# PixelRing.net
KiCad netlist of a schematic drawn in EAGLE
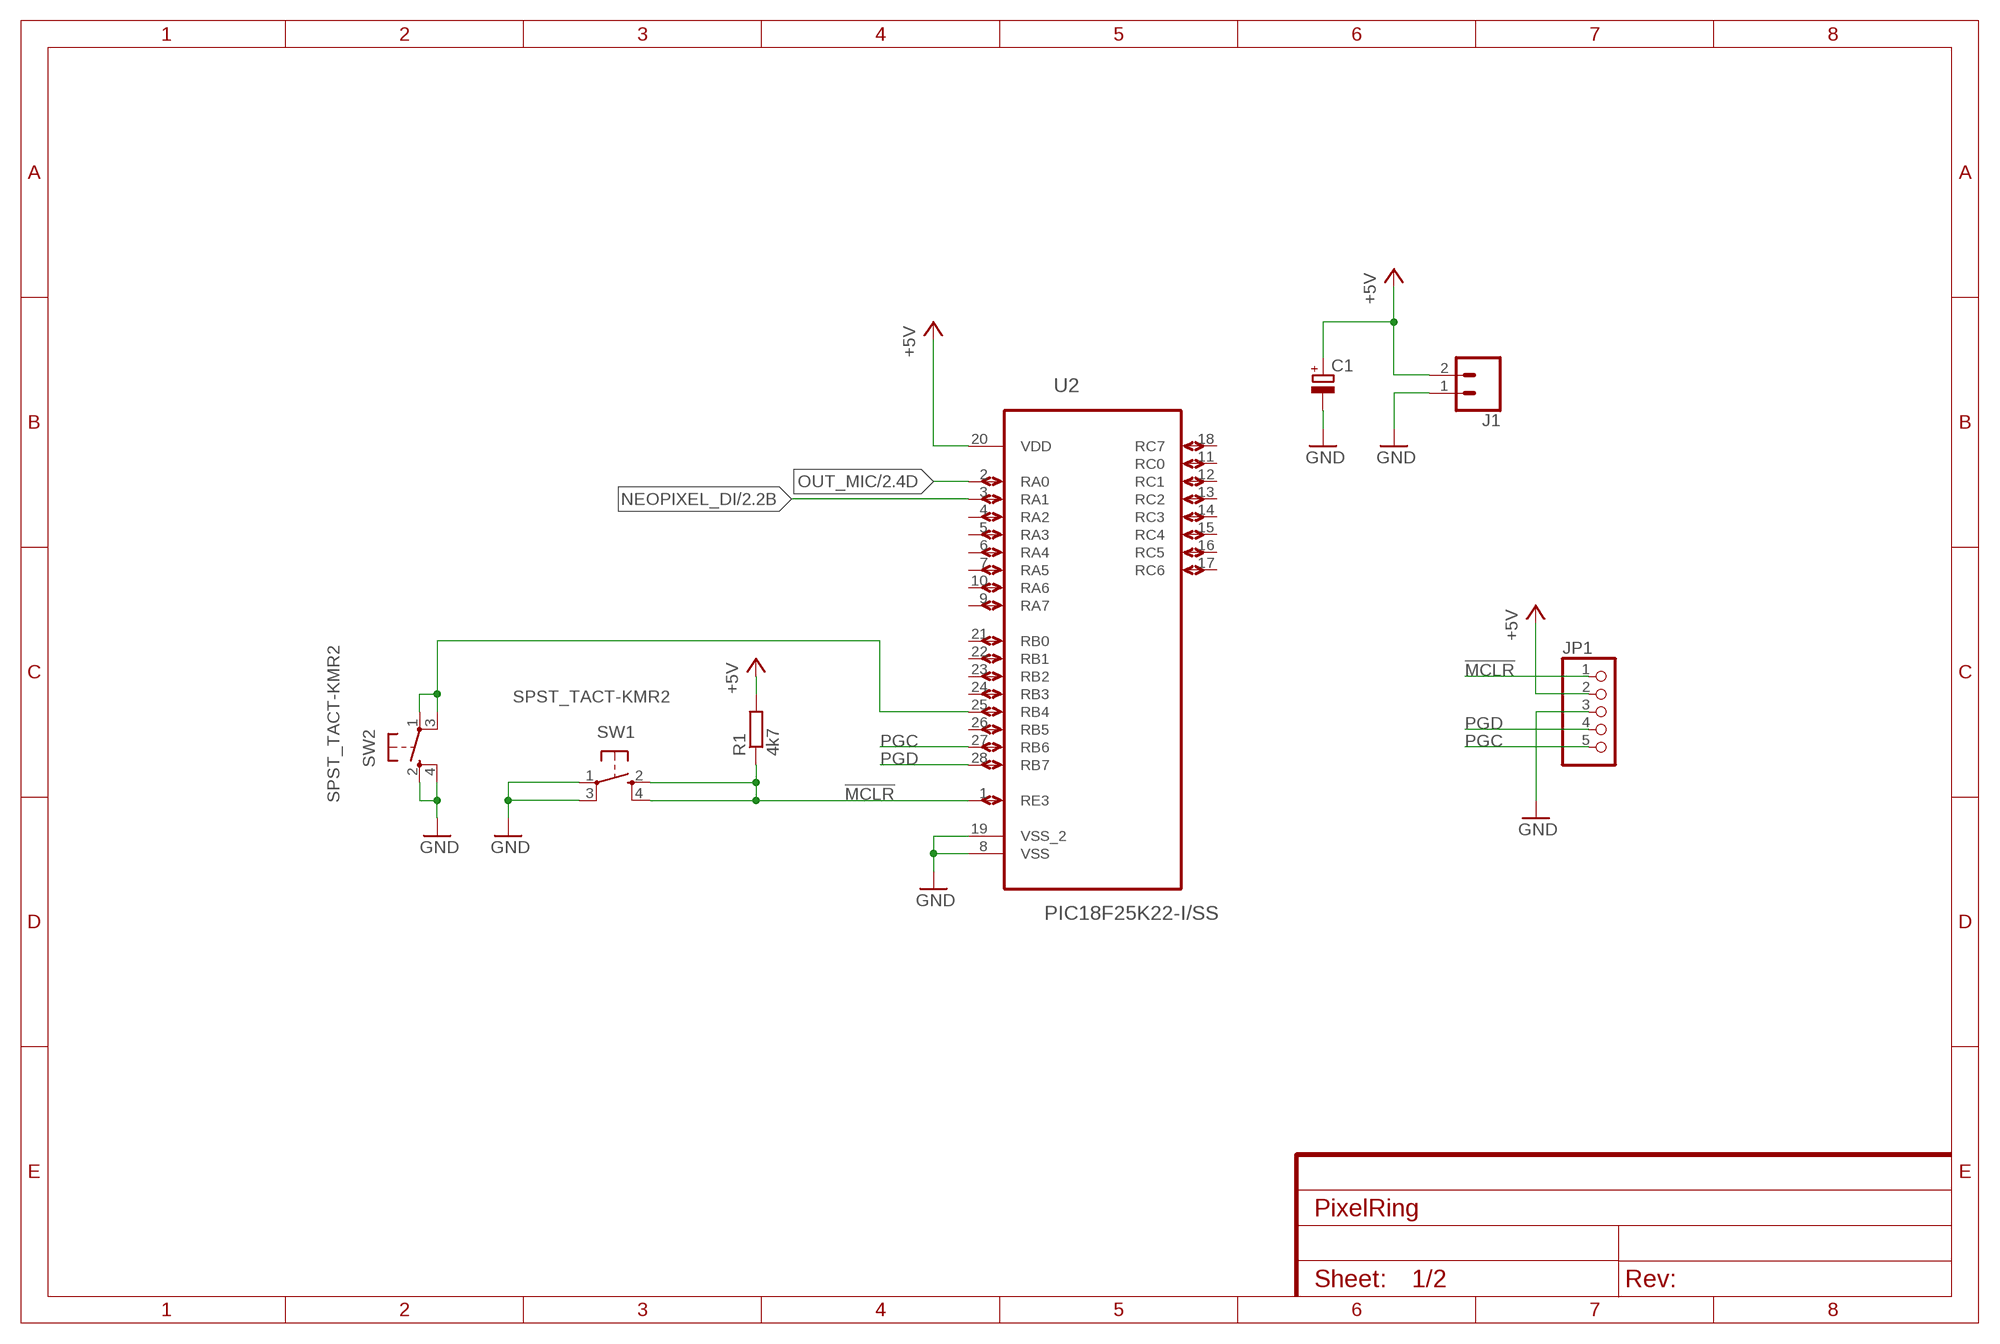
[diagram p0: schematic, sheet 1]
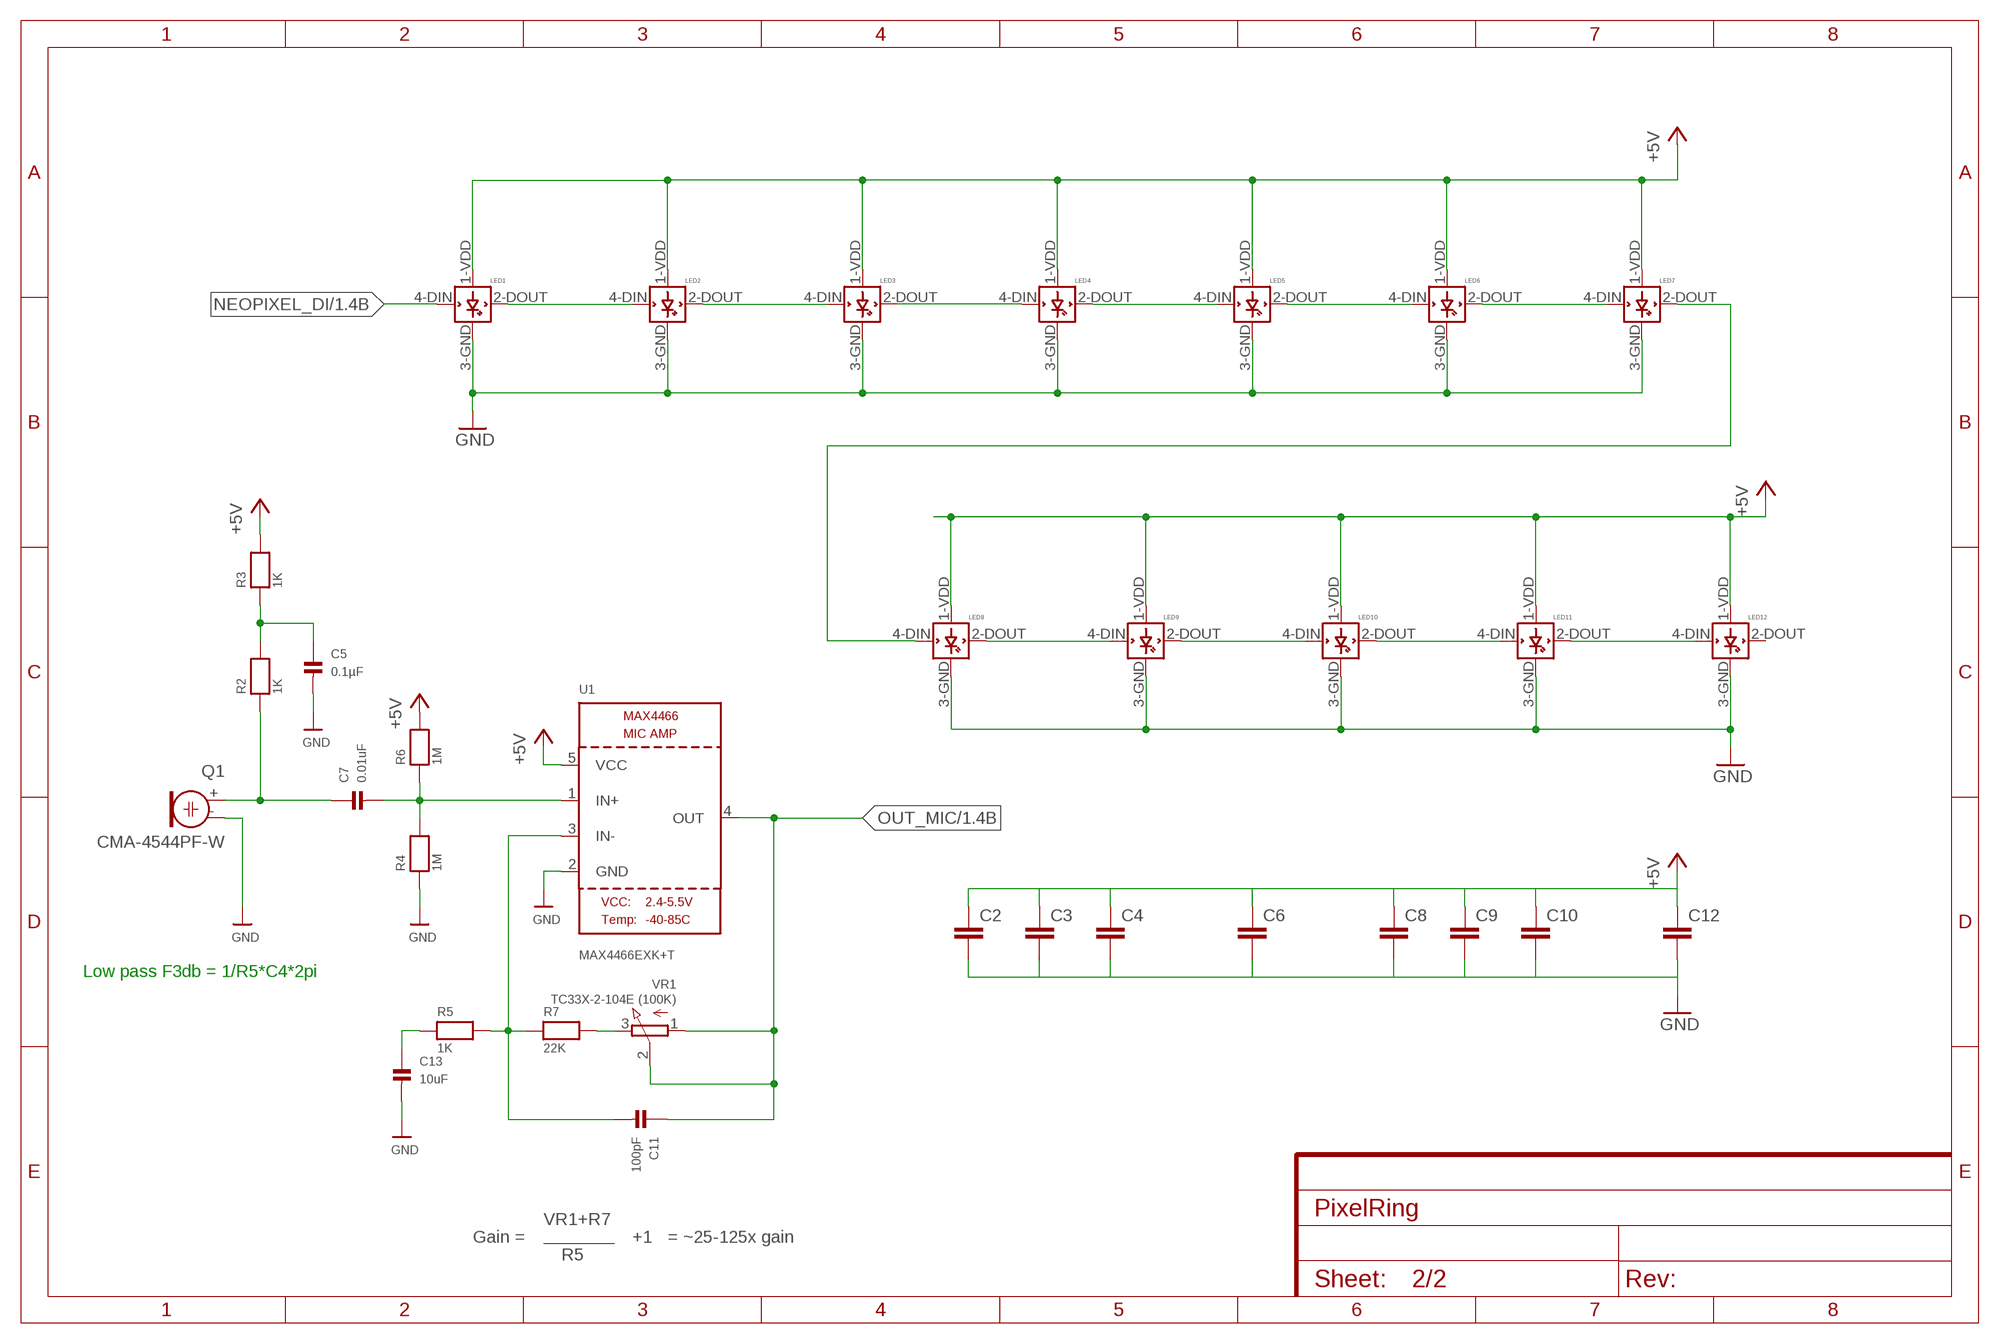
[diagram p1: schematic, sheet 2]

(export (version "E")
  (design (tool "Eeschema 10.0.6"))
  (components
    (comp (ref "C2")
      (value "C-EUC0603")
      (footprint "eagle-import:C0603")
      (libsource (lib "eagle-import") (part "C-EUC0603"))
    )
    (comp (ref "C3")
      (value "C-EUC0603")
      (footprint "eagle-import:C0603")
      (libsource (lib "eagle-import") (part "C-EUC0603"))
    )
    (comp (ref "C4")
      (value "C-EUC0603")
      (footprint "eagle-import:C0603")
      (libsource (lib "eagle-import") (part "C-EUC0603"))
    )
    (comp (ref "C5")
      (value "0.1µF")
      (footprint "eagle-import:0805")
      (libsource (lib "eagle-import") (part "CAP_CERAMIC0805"))
    )
    (comp (ref "C6")
      (value "C-EUC0603")
      (footprint "eagle-import:C0603")
      (libsource (lib "eagle-import") (part "C-EUC0603"))
    )
    (comp (ref "C7")
      (value "0.01uF")
      (footprint "eagle-import:0805")
      (libsource (lib "eagle-import") (part "CAP_CERAMIC0805"))
    )
    (comp (ref "C8")
      (value "C-EUC0603")
      (footprint "eagle-import:C0603")
      (libsource (lib "eagle-import") (part "C-EUC0603"))
    )
    (comp (ref "C9")
      (value "C-EUC0603")
      (footprint "eagle-import:C0603")
      (libsource (lib "eagle-import") (part "C-EUC0603"))
    )
    (comp (ref "C10")
      (value "C-EUC0603")
      (footprint "eagle-import:C0603")
      (libsource (lib "eagle-import") (part "C-EUC0603"))
    )
    (comp (ref "C11")
      (value "100pF")
      (footprint "eagle-import:0805")
      (libsource (lib "eagle-import") (part "CAP_CERAMIC0805"))
    )
    (comp (ref "C12")
      (value "C-EUC0603")
      (footprint "eagle-import:C0603")
      (libsource (lib "eagle-import") (part "C-EUC0603"))
    )
    (comp (ref "C13")
      (value "10uF")
      (footprint "eagle-import:0805")
      (libsource (lib "eagle-import") (part "CAP_CERAMIC0805"))
    )
    (comp (ref "LED1")
      (value "WS2812B")
      (footprint "eagle-import:WS2812B")
      (libsource (lib "eagle-import") (part "WS2812B"))
    )
    (comp (ref "LED2")
      (value "WS2812B")
      (footprint "eagle-import:WS2812B")
      (libsource (lib "eagle-import") (part "WS2812B"))
    )
    (comp (ref "LED3")
      (value "WS2812B")
      (footprint "eagle-import:WS2812B")
      (libsource (lib "eagle-import") (part "WS2812B"))
    )
    (comp (ref "LED4")
      (value "WS2812B")
      (footprint "eagle-import:WS2812B")
      (libsource (lib "eagle-import") (part "WS2812B"))
    )
    (comp (ref "LED5")
      (value "WS2812B")
      (footprint "eagle-import:WS2812B")
      (libsource (lib "eagle-import") (part "WS2812B"))
    )
    (comp (ref "LED6")
      (value "WS2812B")
      (footprint "eagle-import:WS2812B")
      (libsource (lib "eagle-import") (part "WS2812B"))
    )
    (comp (ref "LED7")
      (value "WS2812B")
      (footprint "eagle-import:WS2812B")
      (libsource (lib "eagle-import") (part "WS2812B"))
    )
    (comp (ref "LED8")
      (value "WS2812B")
      (footprint "eagle-import:WS2812B")
      (libsource (lib "eagle-import") (part "WS2812B"))
    )
    (comp (ref "LED9")
      (value "WS2812B")
      (footprint "eagle-import:WS2812B")
      (libsource (lib "eagle-import") (part "WS2812B"))
    )
    (comp (ref "LED10")
      (value "WS2812B")
      (footprint "eagle-import:WS2812B")
      (libsource (lib "eagle-import") (part "WS2812B"))
    )
    (comp (ref "LED11")
      (value "WS2812B")
      (footprint "eagle-import:WS2812B")
      (libsource (lib "eagle-import") (part "WS2812B"))
    )
    (comp (ref "LED12")
      (value "WS2812B")
      (footprint "eagle-import:WS2812B")
      (libsource (lib "eagle-import") (part "WS2812B"))
    )
    (comp (ref "Q1")
      (value "CMA-4544PF-W")
      (footprint "eagle-import:ELECTRET_9.7")
      (libsource (lib "eagle-import") (part "ELECTRET"))
    )
    (comp (ref "R2")
      (value "1K")
      (footprint "eagle-import:0805")
      (libsource (lib "eagle-import") (part "RESISTOR0805"))
    )
    (comp (ref "R3")
      (value "1K")
      (footprint "eagle-import:0805")
      (libsource (lib "eagle-import") (part "RESISTOR0805"))
    )
    (comp (ref "R4")
      (value "1M")
      (footprint "eagle-import:0805")
      (libsource (lib "eagle-import") (part "RESISTOR0805"))
    )
    (comp (ref "R5")
      (value "1K")
      (footprint "eagle-import:0805")
      (libsource (lib "eagle-import") (part "RESISTOR0805"))
    )
    (comp (ref "R6")
      (value "1M")
      (footprint "eagle-import:0805")
      (libsource (lib "eagle-import") (part "RESISTOR0805"))
    )
    (comp (ref "R7")
      (value "22K")
      (footprint "eagle-import:0805")
      (libsource (lib "eagle-import") (part "RESISTOR0805"))
    )
    (comp (ref "U1")
      (value "MAX4466EXK+T")
      (footprint "eagle-import:SC70-5")
      (libsource (lib "eagle-import") (part "MAX4466{dblquote}{dblquote}"))
    )
    (comp (ref "VR1")
      (value "TC33X-2-104E (100K)")
      (footprint "eagle-import:TRIMPOT_BOURNS_TC33X-2")
      (libsource (lib "eagle-import") (part "TRIMPOTTC33X-2"))
    )
    (comp (ref "C1")
      (value "CPOL-EUSMCB")
      (footprint "eagle-import:SMC_B")
      (libsource (lib "eagle-import") (part "CPOL-EUSMCB"))
    )
    (comp (ref "J1")
      (value "CONN_02-JST-2MM-SMT")
      (footprint "eagle-import:JST-2-SMD")
      (libsource (lib "eagle-import") (part "CONN_02-JST-2MM-SMT"))
    )
    (comp (ref "JP1")
      (value "PINHD-1X5")
      (footprint "eagle-import:1X05")
      (libsource (lib "eagle-import") (part "PINHD-1X5"))
    )
    (comp (ref "R1")
      (value "4k7")
      (footprint "eagle-import:R0603")
      (libsource (lib "eagle-import") (part "R-EU_R0603"))
    )
    (comp (ref "SW1")
      (value "SPST_TACT-KMR2")
      (footprint "eagle-import:KMR2")
      (libsource (lib "eagle-import") (part "SPST_TACT-KMR2"))
    )
    (comp (ref "SW2")
      (value "SPST_TACT-KMR2")
      (footprint "eagle-import:KMR2")
      (libsource (lib "eagle-import") (part "SPST_TACT-KMR2"))
    )
    (comp (ref "U2")
      (value "PIC18F25K22-I/SS")
      (footprint "eagle-import:SOP65P780X200-28N")
      (libsource (lib "eagle-import") (part "PIC18F25K22-I/SS"))
    )
  )
  (nets
    (net (code "1") (name "+5V") (class "Default")
      (node (ref "C1") (pin "+") (pinfunction "+_+") (pintype "passive"))
      (node (ref "C10") (pin "1") (pinfunction "1_1") (pintype "passive"))
      (node (ref "C12") (pin "1") (pinfunction "1_1") (pintype "passive"))
      (node (ref "C2") (pin "1") (pinfunction "1_1") (pintype "passive"))
      (node (ref "C3") (pin "1") (pinfunction "1_1") (pintype "passive"))
      (node (ref "C4") (pin "1") (pinfunction "1_1") (pintype "passive"))
      (node (ref "C6") (pin "1") (pinfunction "1_1") (pintype "passive"))
      (node (ref "C8") (pin "1") (pinfunction "1_1") (pintype "passive"))
      (node (ref "C9") (pin "1") (pinfunction "1_1") (pintype "passive"))
      (node (ref "J1") (pin "2") (pinfunction "1_2") (pintype "passive"))
      (node (ref "JP1") (pin "2") (pinfunction "2_2") (pintype "passive"))
      (node (ref "LED1") (pin "1-VDD") (pinfunction "VDD_1-VDD") (pintype "bidirectional"))
      (node (ref "LED10") (pin "1-VDD") (pinfunction "VDD_1-VDD") (pintype "bidirectional"))
      (node (ref "LED11") (pin "1-VDD") (pinfunction "VDD_1-VDD") (pintype "bidirectional"))
      (node (ref "LED12") (pin "1-VDD") (pinfunction "VDD_1-VDD") (pintype "bidirectional"))
      (node (ref "LED2") (pin "1-VDD") (pinfunction "VDD_1-VDD") (pintype "bidirectional"))
      (node (ref "LED3") (pin "1-VDD") (pinfunction "VDD_1-VDD") (pintype "bidirectional"))
      (node (ref "LED4") (pin "1-VDD") (pinfunction "VDD_1-VDD") (pintype "bidirectional"))
      (node (ref "LED5") (pin "1-VDD") (pinfunction "VDD_1-VDD") (pintype "bidirectional"))
      (node (ref "LED6") (pin "1-VDD") (pinfunction "VDD_1-VDD") (pintype "bidirectional"))
      (node (ref "LED7") (pin "1-VDD") (pinfunction "VDD_1-VDD") (pintype "bidirectional"))
      (node (ref "LED8") (pin "1-VDD") (pinfunction "VDD_1-VDD") (pintype "bidirectional"))
      (node (ref "LED9") (pin "1-VDD") (pinfunction "VDD_1-VDD") (pintype "bidirectional"))
      (node (ref "R1") (pin "2") (pinfunction "2_2") (pintype "passive"))
      (node (ref "R3") (pin "2") (pinfunction "2_2") (pintype "passive"))
      (node (ref "R6") (pin "2") (pinfunction "2_2") (pintype "passive"))
      (node (ref "U1") (pin "5") (pinfunction "VCC_5") (pintype "bidirectional"))
      (node (ref "U2") (pin "20") (pinfunction "VDD_20") (pintype "power_in"))
    )
    (net (code "2") (name "GND") (class "Default")
      (node (ref "C1") (pin "-") (pinfunction "-_-") (pintype "passive"))
      (node (ref "C10") (pin "2") (pinfunction "2_2") (pintype "passive"))
      (node (ref "C12") (pin "2") (pinfunction "2_2") (pintype "passive"))
      (node (ref "C13") (pin "2") (pinfunction "P$2_2") (pintype "passive"))
      (node (ref "C2") (pin "2") (pinfunction "2_2") (pintype "passive"))
      (node (ref "C3") (pin "2") (pinfunction "2_2") (pintype "passive"))
      (node (ref "C4") (pin "2") (pinfunction "2_2") (pintype "passive"))
      (node (ref "C5") (pin "2") (pinfunction "P$2_2") (pintype "passive"))
      (node (ref "C6") (pin "2") (pinfunction "2_2") (pintype "passive"))
      (node (ref "C8") (pin "2") (pinfunction "2_2") (pintype "passive"))
      (node (ref "C9") (pin "2") (pinfunction "2_2") (pintype "passive"))
      (node (ref "J1") (pin "1") (pinfunction "2_1") (pintype "passive"))
      (node (ref "JP1") (pin "3") (pinfunction "3_3") (pintype "passive"))
      (node (ref "LED1") (pin "3-GND") (pinfunction "GND_3-GND") (pintype "bidirectional"))
      (node (ref "LED10") (pin "3-GND") (pinfunction "GND_3-GND") (pintype "bidirectional"))
      (node (ref "LED11") (pin "3-GND") (pinfunction "GND_3-GND") (pintype "bidirectional"))
      (node (ref "LED12") (pin "3-GND") (pinfunction "GND_3-GND") (pintype "bidirectional"))
      (node (ref "LED2") (pin "3-GND") (pinfunction "GND_3-GND") (pintype "bidirectional"))
      (node (ref "LED3") (pin "3-GND") (pinfunction "GND_3-GND") (pintype "bidirectional"))
      (node (ref "LED4") (pin "3-GND") (pinfunction "GND_3-GND") (pintype "bidirectional"))
      (node (ref "LED5") (pin "3-GND") (pinfunction "GND_3-GND") (pintype "bidirectional"))
      (node (ref "LED6") (pin "3-GND") (pinfunction "GND_3-GND") (pintype "bidirectional"))
      (node (ref "LED7") (pin "3-GND") (pinfunction "GND_3-GND") (pintype "bidirectional"))
      (node (ref "LED8") (pin "3-GND") (pinfunction "GND_3-GND") (pintype "bidirectional"))
      (node (ref "LED9") (pin "3-GND") (pinfunction "GND_3-GND") (pintype "bidirectional"))
      (node (ref "Q1") (pin "-") (pinfunction "1_-") (pintype "passive"))
      (node (ref "R4") (pin "1") (pinfunction "1_1") (pintype "passive"))
      (node (ref "SW1") (pin "1") (pinfunction "P_1") (pintype "passive"))
      (node (ref "SW1") (pin "3") (pinfunction "P1_3") (pintype "passive"))
      (node (ref "SW2") (pin "2") (pinfunction "S_2") (pintype "passive"))
      (node (ref "SW2") (pin "4") (pinfunction "S1_4") (pintype "passive"))
      (node (ref "U1") (pin "2") (pinfunction "GND_2") (pintype "bidirectional"))
      (node (ref "U2") (pin "19") (pinfunction "VSS_2_19") (pintype "power_in"))
      (node (ref "U2") (pin "8") (pinfunction "VSS_8") (pintype "power_in"))
    )
    (net (code "3") (name "NEOPIXEL_DI") (class "Default")
      (node (ref "LED1") (pin "4-DIN") (pinfunction "DIN_4-DIN") (pintype "input"))
      (node (ref "U2") (pin "3") (pinfunction "RA1_3") (pintype "bidirectional"))
    )
    (net (code "4") (name "Net-(C5-P$1)") (class "Default")
      (node (ref "C5") (pin "1") (pinfunction "P$1_1") (pintype "passive"))
      (node (ref "R2") (pin "2") (pinfunction "2_2") (pintype "passive"))
      (node (ref "R3") (pin "1") (pinfunction "1_1") (pintype "passive"))
    )
    (net (code "5") (name "Net-(C7-P$1)") (class "Default")
      (node (ref "C7") (pin "1") (pinfunction "P$1_1") (pintype "passive"))
      (node (ref "Q1") (pin "+") (pinfunction "2_+") (pintype "passive"))
      (node (ref "R2") (pin "1") (pinfunction "1_1") (pintype "passive"))
    )
    (net (code "6") (name "Net-(C7-P$2)") (class "Default")
      (node (ref "C7") (pin "2") (pinfunction "P$2_2") (pintype "passive"))
      (node (ref "R4") (pin "2") (pinfunction "2_2") (pintype "passive"))
      (node (ref "R6") (pin "1") (pinfunction "1_1") (pintype "passive"))
      (node (ref "U1") (pin "1") (pinfunction "IN+_1") (pintype "bidirectional"))
    )
    (net (code "7") (name "Net-(C11-P$2)") (class "Default")
      (node (ref "C11") (pin "2") (pinfunction "P$2_2") (pintype "passive"))
      (node (ref "R5") (pin "2") (pinfunction "2_2") (pintype "passive"))
      (node (ref "R7") (pin "1") (pinfunction "1_1") (pintype "passive"))
      (node (ref "U1") (pin "3") (pinfunction "IN-_3") (pintype "bidirectional"))
    )
    (net (code "8") (name "Net-(C13-P$1)") (class "Default")
      (node (ref "C13") (pin "1") (pinfunction "P$1_1") (pintype "passive"))
      (node (ref "R5") (pin "1") (pinfunction "1_1") (pintype "passive"))
    )
    (net (code "9") (name "Net-(LED1-DOUT)") (class "Default")
      (node (ref "LED1") (pin "2-DOUT") (pinfunction "DOUT_2-DOUT") (pintype "output"))
      (node (ref "LED2") (pin "4-DIN") (pinfunction "DIN_4-DIN") (pintype "input"))
    )
    (net (code "10") (name "Net-(LED2-DOUT)") (class "Default")
      (node (ref "LED2") (pin "2-DOUT") (pinfunction "DOUT_2-DOUT") (pintype "output"))
      (node (ref "LED3") (pin "4-DIN") (pinfunction "DIN_4-DIN") (pintype "input"))
    )
    (net (code "11") (name "Net-(LED3-DOUT)") (class "Default")
      (node (ref "LED3") (pin "2-DOUT") (pinfunction "DOUT_2-DOUT") (pintype "output"))
      (node (ref "LED4") (pin "4-DIN") (pinfunction "DIN_4-DIN") (pintype "input"))
    )
    (net (code "12") (name "Net-(LED4-DOUT)") (class "Default")
      (node (ref "LED4") (pin "2-DOUT") (pinfunction "DOUT_2-DOUT") (pintype "output"))
      (node (ref "LED5") (pin "4-DIN") (pinfunction "DIN_4-DIN") (pintype "input"))
    )
    (net (code "13") (name "Net-(LED5-DOUT)") (class "Default")
      (node (ref "LED5") (pin "2-DOUT") (pinfunction "DOUT_2-DOUT") (pintype "output"))
      (node (ref "LED6") (pin "4-DIN") (pinfunction "DIN_4-DIN") (pintype "input"))
    )
    (net (code "14") (name "Net-(LED6-DOUT)") (class "Default")
      (node (ref "LED6") (pin "2-DOUT") (pinfunction "DOUT_2-DOUT") (pintype "output"))
      (node (ref "LED7") (pin "4-DIN") (pinfunction "DIN_4-DIN") (pintype "input"))
    )
    (net (code "15") (name "Net-(LED7-DOUT)") (class "Default")
      (node (ref "LED7") (pin "2-DOUT") (pinfunction "DOUT_2-DOUT") (pintype "output"))
      (node (ref "LED8") (pin "4-DIN") (pinfunction "DIN_4-DIN") (pintype "input"))
    )
    (net (code "16") (name "Net-(LED8-DOUT)") (class "Default")
      (node (ref "LED8") (pin "2-DOUT") (pinfunction "DOUT_2-DOUT") (pintype "output"))
      (node (ref "LED9") (pin "4-DIN") (pinfunction "DIN_4-DIN") (pintype "input"))
    )
    (net (code "17") (name "Net-(LED10-DIN)") (class "Default")
      (node (ref "LED10") (pin "4-DIN") (pinfunction "DIN_4-DIN") (pintype "input"))
      (node (ref "LED9") (pin "2-DOUT") (pinfunction "DOUT_2-DOUT") (pintype "output"))
    )
    (net (code "18") (name "Net-(LED10-DOUT)") (class "Default")
      (node (ref "LED10") (pin "2-DOUT") (pinfunction "DOUT_2-DOUT") (pintype "output"))
      (node (ref "LED11") (pin "4-DIN") (pinfunction "DIN_4-DIN") (pintype "input"))
    )
    (net (code "19") (name "Net-(LED11-DOUT)") (class "Default")
      (node (ref "LED11") (pin "2-DOUT") (pinfunction "DOUT_2-DOUT") (pintype "output"))
      (node (ref "LED12") (pin "4-DIN") (pinfunction "DIN_4-DIN") (pintype "input"))
    )
    (net (code "20") (name "Net-(SW2-P)") (class "Default")
      (node (ref "SW2") (pin "1") (pinfunction "P_1") (pintype "passive"))
      (node (ref "SW2") (pin "3") (pinfunction "P1_3") (pintype "passive"))
      (node (ref "U2") (pin "25") (pinfunction "RB4_25") (pintype "bidirectional"))
    )
    (net (code "21") (name "Net-(VR1-E)") (class "Default")
      (node (ref "R7") (pin "2") (pinfunction "2_2") (pintype "passive"))
      (node (ref "VR1") (pin "3") (pinfunction "E_3") (pintype "passive"))
    )
    (net (code "22") (name "OUT_MIC") (class "Default")
      (node (ref "C11") (pin "1") (pinfunction "P$1_1") (pintype "passive"))
      (node (ref "U1") (pin "4") (pinfunction "OUT_4") (pintype "bidirectional"))
      (node (ref "U2") (pin "2") (pinfunction "RA0_2") (pintype "bidirectional"))
      (node (ref "VR1") (pin "1") (pinfunction "A_1") (pintype "passive"))
      (node (ref "VR1") (pin "2") (pinfunction "S_2") (pintype "passive"))
    )
    (net (code "23") (name "PGC") (class "Default")
      (node (ref "JP1") (pin "5") (pinfunction "5_5") (pintype "passive"))
      (node (ref "U2") (pin "27") (pinfunction "RB6_27") (pintype "bidirectional"))
    )
    (net (code "24") (name "PGD") (class "Default")
      (node (ref "JP1") (pin "4") (pinfunction "4_4") (pintype "passive"))
      (node (ref "U2") (pin "28") (pinfunction "RB7_28") (pintype "bidirectional"))
    )
    (net (code "25") (name "unconnected-(LED12-DOUT-Pad2-DOUT)") (class "Default")
      (node (ref "LED12") (pin "2-DOUT") (pinfunction "DOUT_2-DOUT") (pintype "output"))
    )
    (net (code "26") (name "unconnected-(U2-RA2-Pad4)") (class "Default")
      (node (ref "U2") (pin "4") (pinfunction "RA2_4") (pintype "bidirectional"))
    )
    (net (code "27") (name "unconnected-(U2-RA3-Pad5)") (class "Default")
      (node (ref "U2") (pin "5") (pinfunction "RA3_5") (pintype "bidirectional"))
    )
    (net (code "28") (name "unconnected-(U2-RA4-Pad6)") (class "Default")
      (node (ref "U2") (pin "6") (pinfunction "RA4_6") (pintype "bidirectional"))
    )
    (net (code "29") (name "unconnected-(U2-RA5-Pad7)") (class "Default")
      (node (ref "U2") (pin "7") (pinfunction "RA5_7") (pintype "bidirectional"))
    )
    (net (code "30") (name "unconnected-(U2-RA6-Pad10)") (class "Default")
      (node (ref "U2") (pin "10") (pinfunction "RA6_10") (pintype "bidirectional"))
    )
    (net (code "31") (name "unconnected-(U2-RA7-Pad9)") (class "Default")
      (node (ref "U2") (pin "9") (pinfunction "RA7_9") (pintype "bidirectional"))
    )
    (net (code "32") (name "unconnected-(U2-RB0-Pad21)") (class "Default")
      (node (ref "U2") (pin "21") (pinfunction "RB0_21") (pintype "bidirectional"))
    )
    (net (code "33") (name "unconnected-(U2-RB1-Pad22)") (class "Default")
      (node (ref "U2") (pin "22") (pinfunction "RB1_22") (pintype "bidirectional"))
    )
    (net (code "34") (name "unconnected-(U2-RB2-Pad23)") (class "Default")
      (node (ref "U2") (pin "23") (pinfunction "RB2_23") (pintype "bidirectional"))
    )
    (net (code "35") (name "unconnected-(U2-RB3-Pad24)") (class "Default")
      (node (ref "U2") (pin "24") (pinfunction "RB3_24") (pintype "bidirectional"))
    )
    (net (code "36") (name "unconnected-(U2-RB5-Pad26)") (class "Default")
      (node (ref "U2") (pin "26") (pinfunction "RB5_26") (pintype "bidirectional"))
    )
    (net (code "37") (name "unconnected-(U2-RC0-Pad11)") (class "Default")
      (node (ref "U2") (pin "11") (pinfunction "RC0_11") (pintype "bidirectional"))
    )
    (net (code "38") (name "unconnected-(U2-RC1-Pad12)") (class "Default")
      (node (ref "U2") (pin "12") (pinfunction "RC1_12") (pintype "bidirectional"))
    )
    (net (code "39") (name "unconnected-(U2-RC2-Pad13)") (class "Default")
      (node (ref "U2") (pin "13") (pinfunction "RC2_13") (pintype "bidirectional"))
    )
    (net (code "40") (name "unconnected-(U2-RC3-Pad14)") (class "Default")
      (node (ref "U2") (pin "14") (pinfunction "RC3_14") (pintype "bidirectional"))
    )
    (net (code "41") (name "unconnected-(U2-RC4-Pad15)") (class "Default")
      (node (ref "U2") (pin "15") (pinfunction "RC4_15") (pintype "bidirectional"))
    )
    (net (code "42") (name "unconnected-(U2-RC5-Pad16)") (class "Default")
      (node (ref "U2") (pin "16") (pinfunction "RC5_16") (pintype "bidirectional"))
    )
    (net (code "43") (name "unconnected-(U2-RC6-Pad17)") (class "Default")
      (node (ref "U2") (pin "17") (pinfunction "RC6_17") (pintype "bidirectional"))
    )
    (net (code "44") (name "unconnected-(U2-RC7-Pad18)") (class "Default")
      (node (ref "U2") (pin "18") (pinfunction "RC7_18") (pintype "bidirectional"))
    )
    (net (code "45") (name "~{MCLR}") (class "Default")
      (node (ref "JP1") (pin "1") (pinfunction "1_1") (pintype "passive"))
      (node (ref "R1") (pin "1") (pinfunction "1_1") (pintype "passive"))
      (node (ref "SW1") (pin "2") (pinfunction "S_2") (pintype "passive"))
      (node (ref "SW1") (pin "4") (pinfunction "S1_4") (pintype "passive"))
      (node (ref "U2") (pin "1") (pinfunction "RE3_1") (pintype "input"))
    )
  )
)
